# ESP32_CAN_V2-out.net
KiCad netlist of a schematic drawn in Altium Designer
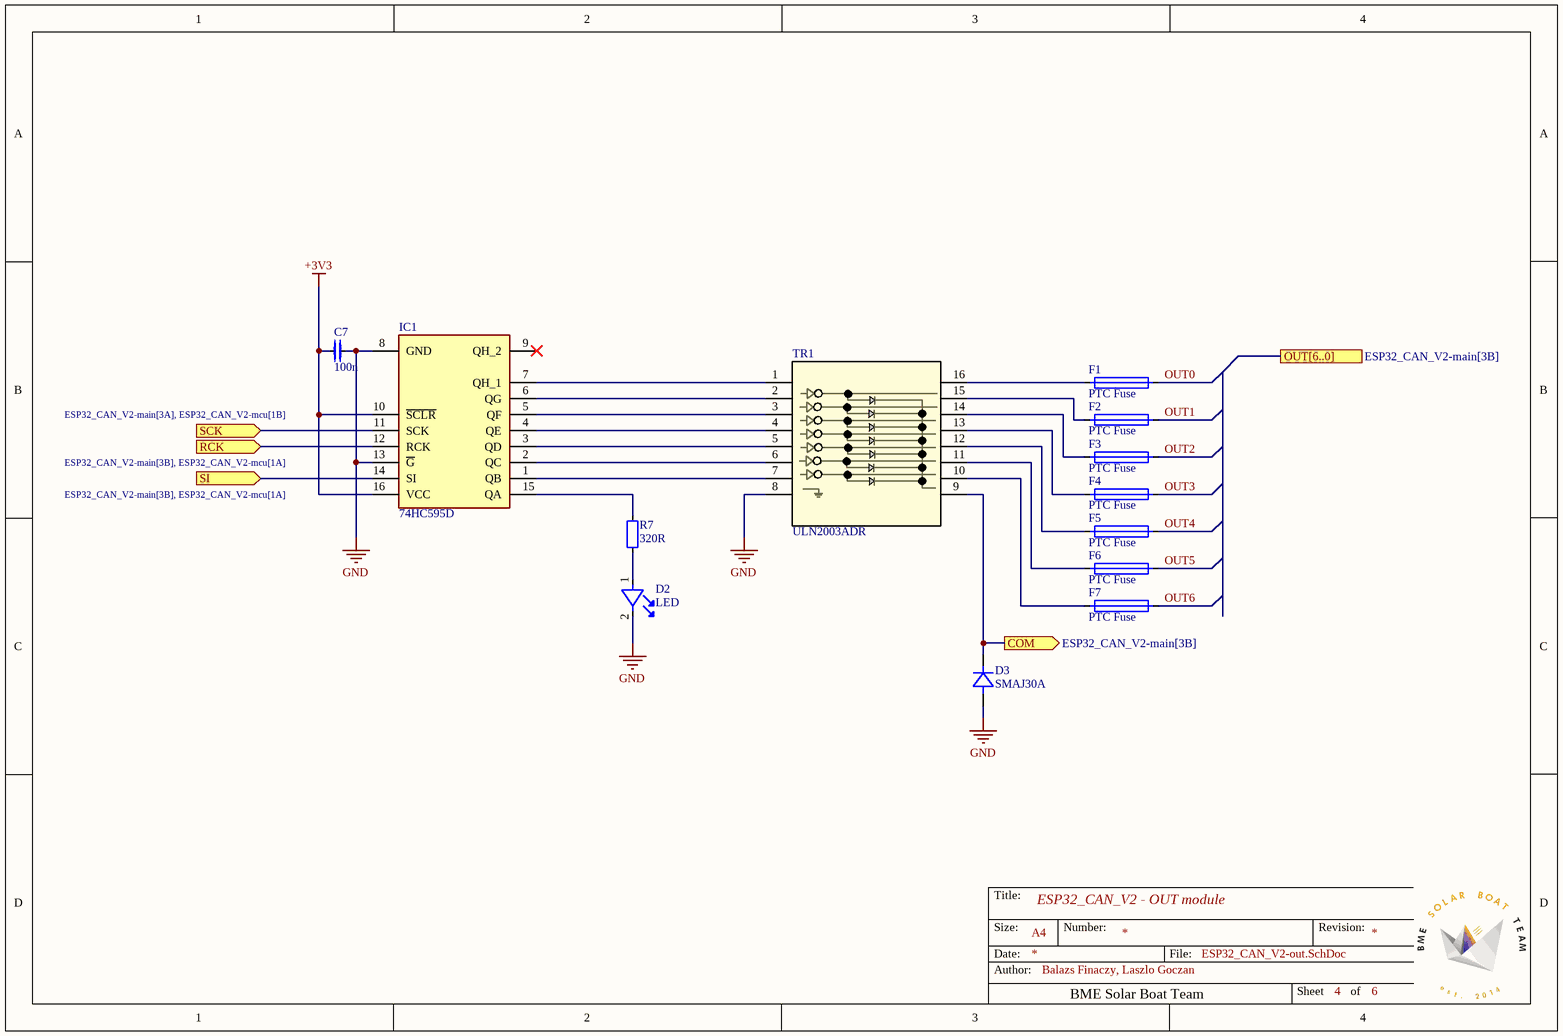
[diagram p0: ESP32_CAN_V2-out.SchDoc]

(export (version "E")
  (design (tool "Eeschema 10.0.6"))
  (components
    (comp (ref "C7") (value "100n") (footprint "C0603") (libsource (lib "ESP32_CAN_V2") (part "C")))
    (comp (ref "D2")
      (value "LED")
      (footprint "LED")
      (description "150060BS83000")
      (libsource (lib "ESP32_CAN_V2") (part "LED"))
    )
    (comp (ref "D3")
      (value "SMAJ30A")
      (footprint "SMASeries_LTF")
      (description "No Description Available")
      (fields (field (name "COPYRIGHT") "Copyright (C) 2026 Ultra Librarian. All rights reserved."))
      (libsource (lib "ESP32_CAN_V2") (part "SMAJ30A"))
    )
    (comp (ref "F1")
      (value "PTC Fuse")
      (footprint "PTSAHT120624V050")
      (description "PTSAHT1206")
      (libsource (lib "ESP32_CAN_V2") (part "PTC Fuse"))
    )
    (comp (ref "F2")
      (value "PTC Fuse")
      (footprint "PTSAHT120624V050")
      (description "PTSAHT1206")
      (libsource (lib "ESP32_CAN_V2") (part "PTC Fuse"))
    )
    (comp (ref "F3")
      (value "PTC Fuse")
      (footprint "PTSAHT120624V050")
      (description "PTSAHT1206")
      (libsource (lib "ESP32_CAN_V2") (part "PTC Fuse"))
    )
    (comp (ref "F4")
      (value "PTC Fuse")
      (footprint "PTSAHT120624V050")
      (description "PTSAHT1206")
      (libsource (lib "ESP32_CAN_V2") (part "PTC Fuse"))
    )
    (comp (ref "F5")
      (value "PTC Fuse")
      (footprint "PTSAHT120624V050")
      (description "PTSAHT1206")
      (libsource (lib "ESP32_CAN_V2") (part "PTC Fuse"))
    )
    (comp (ref "F6")
      (value "PTC Fuse")
      (footprint "PTSAHT120624V050")
      (description "PTSAHT1206")
      (libsource (lib "ESP32_CAN_V2") (part "PTC Fuse"))
    )
    (comp (ref "F7")
      (value "PTC Fuse")
      (footprint "PTSAHT120624V050")
      (description "PTSAHT1206")
      (libsource (lib "ESP32_CAN_V2") (part "PTC Fuse"))
    )
    (comp (ref "IC1")
      (value "74HC595D")
      (footprint "SOIC127P600X175-16N")
      (description "Shift Register Single 8-Bit Serial to Serial/Parallel 16-Pin SOIC T/R")
      (fields (field (name "MOUSER PART NUMBER") "757-74HC595D"))
      (libsource (lib "ESP32_CAN_V2") (part "74HC595D"))
    )
    (comp (ref "R7") (value "320R") (footprint "R0603") (libsource (lib "ESP32_CAN_V2") (part "R")))
    (comp (ref "TR1")
      (value "ULN2003ADR")
      (footprint "ULN2003ADR2G_OSI")
      (description "No Description Available")
      (fields
        (field (name "MANUFACTURER_PART_NUMBER") "ULN2003ADR2G")
        (field (name "COPYRIGHT") "Copyright (C) 2026 Ultra Librarian. All rights reserved.")
      )
      (libsource (lib "ESP32_CAN_V2") (part "ULN2003ADR2G"))
    )
  )
  (nets
    (net (code "1") (name "+3V3") (class "Default")
      (node (ref "C7") (pin "1") (pinfunction "1_1") (pintype "passive"))
      (node (ref "IC1") (pin "10") (pinfunction "~{SCLR}_10") (pintype "passive"))
      (node (ref "IC1") (pin "16") (pinfunction "VCC_16") (pintype "passive"))
    )
    (net (code "2") (name "/COM") (class "Default")
      (node (ref "D3") (pin "1") (pinfunction "1_1") (pintype "passive"))
      (node (ref "TR1") (pin "9") (pinfunction "9_9") (pintype "passive"))
    )
    (net (code "3") (name "/OUT0") (class "Default")
      (node (ref "F1") (pin "2") (pinfunction "2_2") (pintype "passive"))
    )
    (net (code "4") (name "/OUT1") (class "Default")
      (node (ref "F2") (pin "2") (pinfunction "2_2") (pintype "passive"))
    )
    (net (code "5") (name "/OUT2") (class "Default")
      (node (ref "F3") (pin "2") (pinfunction "2_2") (pintype "passive"))
    )
    (net (code "6") (name "/OUT3") (class "Default")
      (node (ref "F4") (pin "2") (pinfunction "2_2") (pintype "passive"))
    )
    (net (code "7") (name "/OUT4") (class "Default")
      (node (ref "F5") (pin "2") (pinfunction "2_2") (pintype "passive"))
    )
    (net (code "8") (name "/OUT5") (class "Default")
      (node (ref "F6") (pin "2") (pinfunction "2_2") (pintype "passive"))
    )
    (net (code "9") (name "/OUT6") (class "Default")
      (node (ref "F7") (pin "2") (pinfunction "2_2") (pintype "passive"))
    )
    (net (code "11") (name "/RCK") (class "Default")
      (node (ref "IC1") (pin "12") (pinfunction "RCK_12") (pintype "passive"))
    )
    (net (code "12") (name "/SCK") (class "Default")
      (node (ref "IC1") (pin "11") (pinfunction "SCK_11") (pintype "passive"))
    )
    (net (code "13") (name "/SI") (class "Default")
      (node (ref "IC1") (pin "14") (pinfunction "SI_14") (pintype "passive"))
    )
    (net (code "14") (name "GND") (class "Default")
      (node (ref "C7") (pin "2") (pinfunction "2_2") (pintype "passive"))
      (node (ref "D2") (pin "2") (pinfunction "2_2") (pintype "passive"))
      (node (ref "D3") (pin "2") (pinfunction "2_2") (pintype "passive"))
      (node (ref "IC1") (pin "13") (pinfunction "~{G}_13") (pintype "passive"))
      (node (ref "IC1") (pin "8") (pinfunction "GND_8") (pintype "passive"))
      (node (ref "TR1") (pin "8") (pinfunction "8_8") (pintype "passive"))
    )
    (net (code "15") (name "Net-(F1-Pad1)") (class "Default")
      (node (ref "F1") (pin "1") (pinfunction "1_1") (pintype "passive"))
      (node (ref "TR1") (pin "16") (pinfunction "16_16") (pintype "passive"))
    )
    (net (code "16") (name "Net-(F2-Pad1)") (class "Default")
      (node (ref "F2") (pin "1") (pinfunction "1_1") (pintype "passive"))
      (node (ref "TR1") (pin "15") (pinfunction "15_15") (pintype "passive"))
    )
    (net (code "17") (name "Net-(F3-Pad1)") (class "Default")
      (node (ref "F3") (pin "1") (pinfunction "1_1") (pintype "passive"))
      (node (ref "TR1") (pin "14") (pinfunction "14_14") (pintype "passive"))
    )
    (net (code "18") (name "Net-(F4-Pad1)") (class "Default")
      (node (ref "F4") (pin "1") (pinfunction "1_1") (pintype "passive"))
      (node (ref "TR1") (pin "13") (pinfunction "13_13") (pintype "passive"))
    )
    (net (code "19") (name "Net-(F5-Pad1)") (class "Default")
      (node (ref "F5") (pin "1") (pinfunction "1_1") (pintype "passive"))
      (node (ref "TR1") (pin "12") (pinfunction "12_12") (pintype "passive"))
    )
    (net (code "20") (name "Net-(F6-Pad1)") (class "Default")
      (node (ref "F6") (pin "1") (pinfunction "1_1") (pintype "passive"))
      (node (ref "TR1") (pin "11") (pinfunction "11_11") (pintype "passive"))
    )
    (net (code "21") (name "Net-(F7-Pad1)") (class "Default")
      (node (ref "F7") (pin "1") (pinfunction "1_1") (pintype "passive"))
      (node (ref "TR1") (pin "10") (pinfunction "10_10") (pintype "passive"))
    )
    (net (code "22") (name "Net-(IC1-QA)") (class "Default")
      (node (ref "IC1") (pin "15") (pinfunction "QA_15") (pintype "passive"))
      (node (ref "R7") (pin "1") (pinfunction "0_1") (pintype "passive"))
    )
    (net (code "23") (name "Net-(IC1-QB)") (class "Default")
      (node (ref "IC1") (pin "1") (pinfunction "QB_1") (pintype "passive"))
      (node (ref "TR1") (pin "7") (pinfunction "7_7") (pintype "passive"))
    )
    (net (code "24") (name "Net-(IC1-QC)") (class "Default")
      (node (ref "IC1") (pin "2") (pinfunction "QC_2") (pintype "passive"))
      (node (ref "TR1") (pin "6") (pinfunction "6_6") (pintype "passive"))
    )
    (net (code "25") (name "Net-(IC1-QD)") (class "Default")
      (node (ref "IC1") (pin "3") (pinfunction "QD_3") (pintype "passive"))
      (node (ref "TR1") (pin "5") (pinfunction "5_5") (pintype "passive"))
    )
    (net (code "26") (name "Net-(IC1-QE)") (class "Default")
      (node (ref "IC1") (pin "4") (pinfunction "QE_4") (pintype "passive"))
      (node (ref "TR1") (pin "4") (pinfunction "4_4") (pintype "passive"))
    )
    (net (code "27") (name "Net-(IC1-QF)") (class "Default")
      (node (ref "IC1") (pin "5") (pinfunction "QF_5") (pintype "passive"))
      (node (ref "TR1") (pin "3") (pinfunction "3_3") (pintype "passive"))
    )
    (net (code "28") (name "Net-(IC1-QG)") (class "Default")
      (node (ref "IC1") (pin "6") (pinfunction "QG_6") (pintype "passive"))
      (node (ref "TR1") (pin "2") (pinfunction "2_2") (pintype "passive"))
    )
    (net (code "29") (name "Net-(IC1-QH_1)") (class "Default")
      (node (ref "IC1") (pin "7") (pinfunction "QH_1_7") (pintype "passive"))
      (node (ref "TR1") (pin "1") (pinfunction "1_1") (pintype "passive"))
    )
    (net (code "30") (name "Net-(R7-1)") (class "Default")
      (node (ref "D2") (pin "1") (pinfunction "1_1") (pintype "passive"))
      (node (ref "R7") (pin "2") (pinfunction "1_2") (pintype "passive"))
    )
    (net (code "31") (name "unconnected-(IC1-QH_2-Pad9)") (class "Default")
      (node (ref "IC1") (pin "9") (pinfunction "QH_2_9") (pintype "passive+no_connect"))
    )
  )
)
